# board.net
KiCad netlist of a schematic drawn in EAGLE
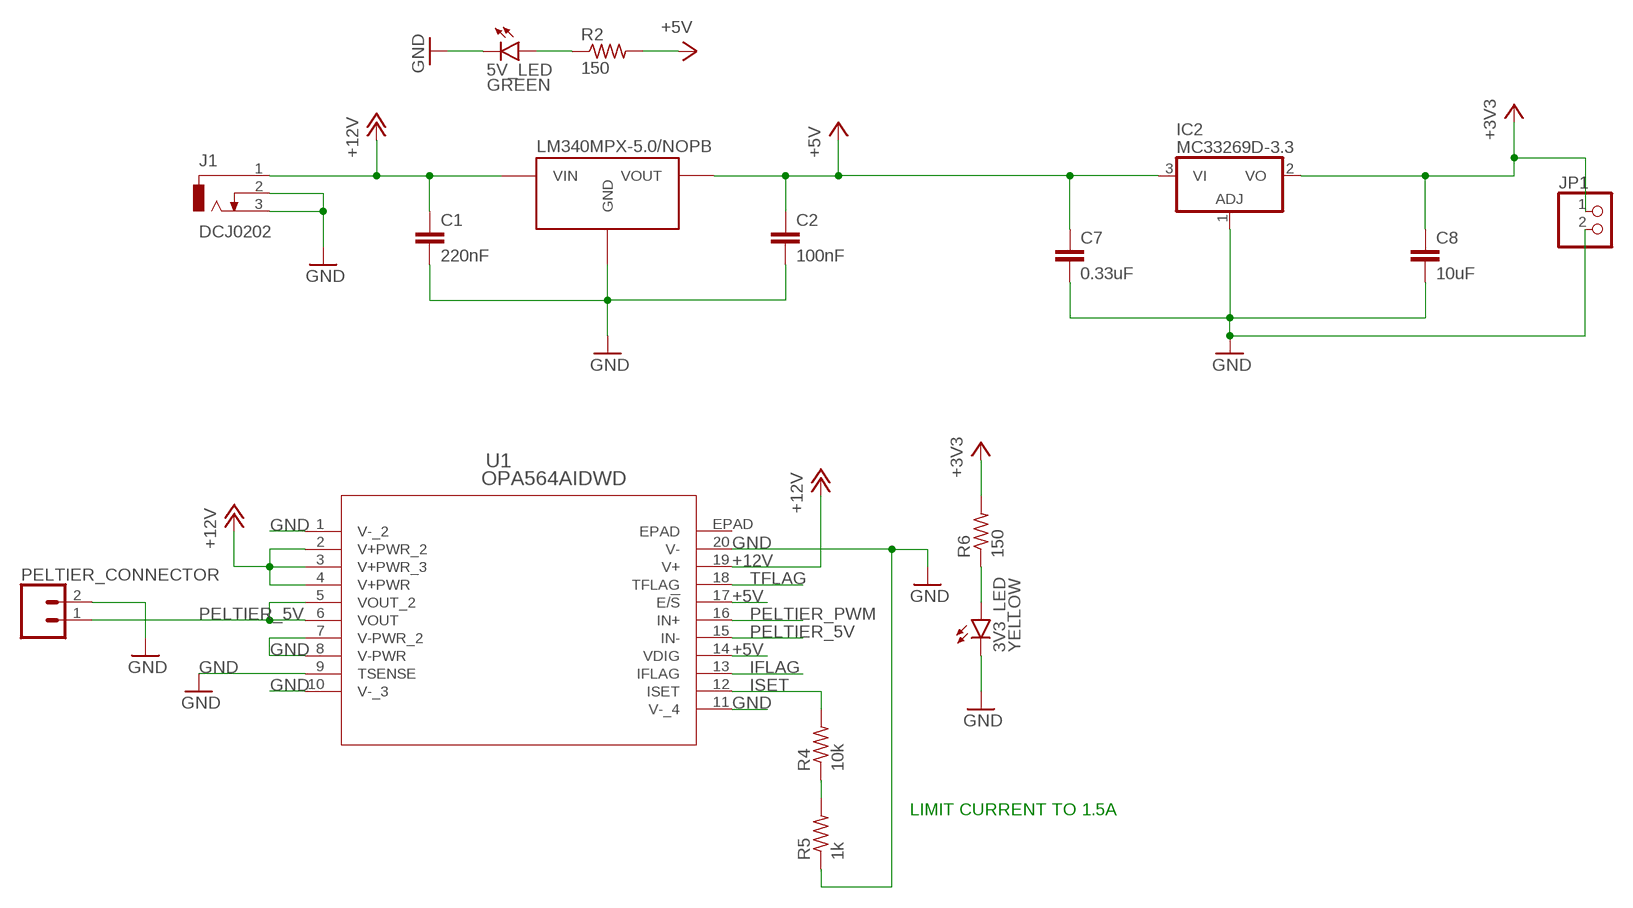
[diagram p0: schematic, sheet 1]
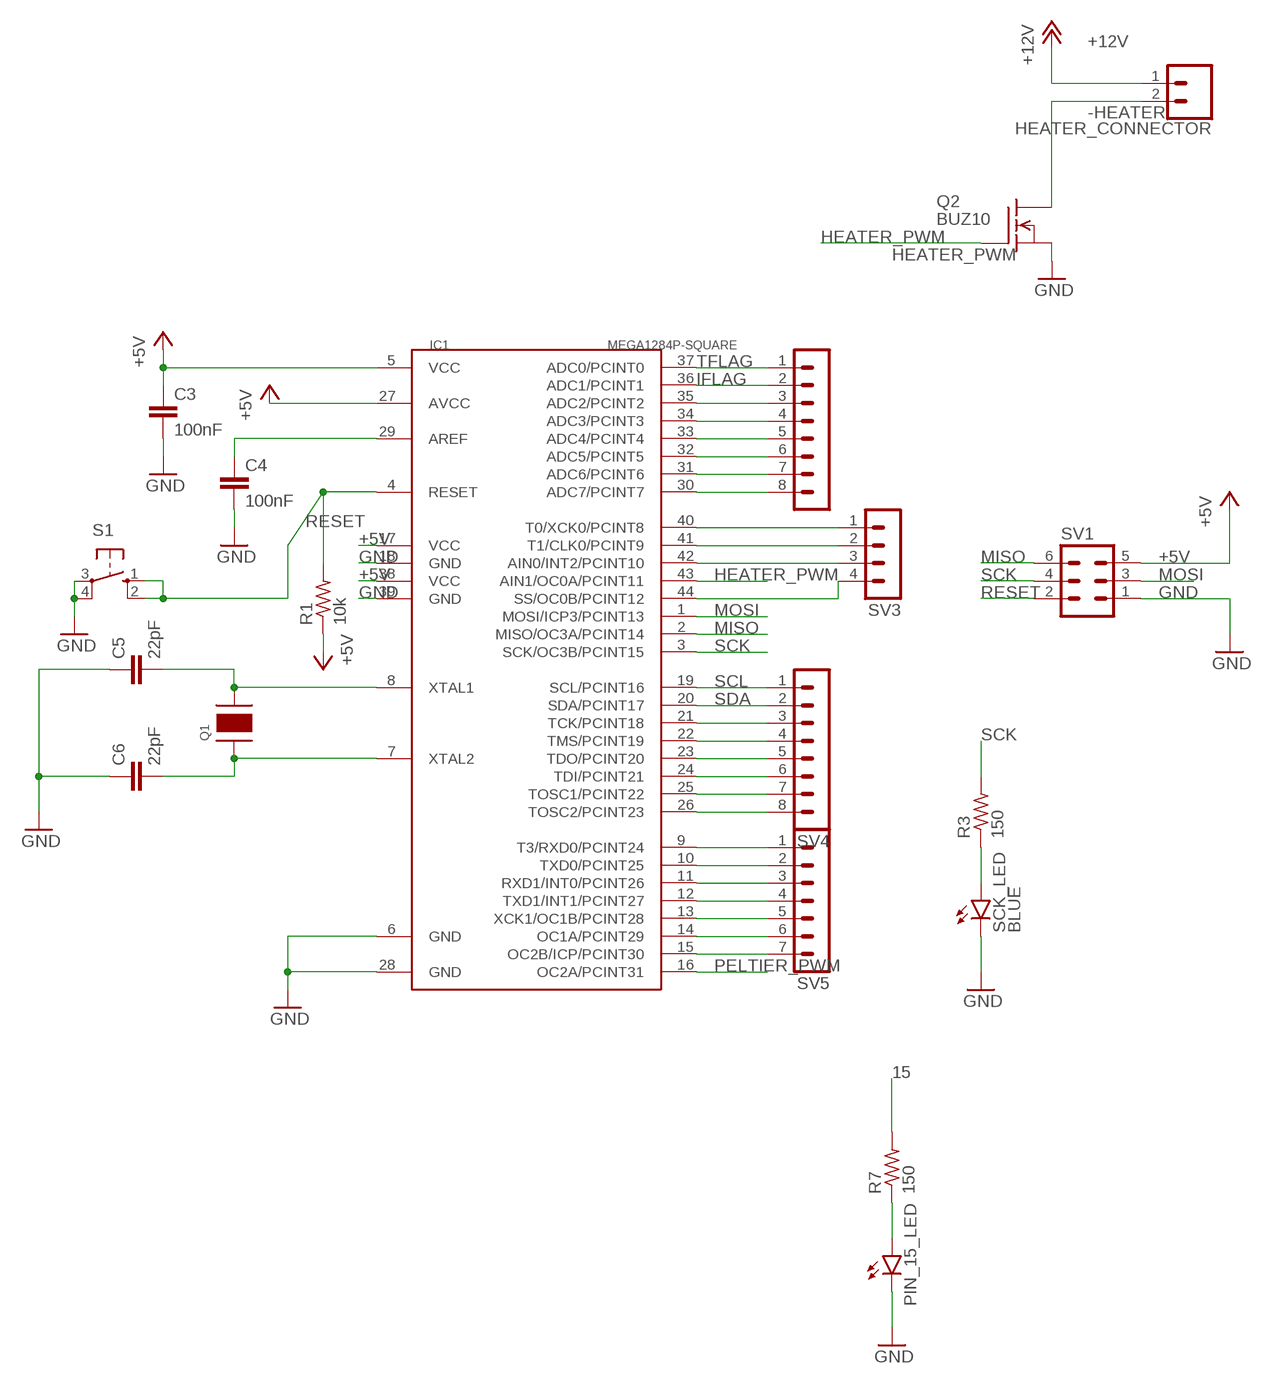
[diagram p1: schematic, sheet 2]

(export (version "E")
  (design (tool "Eeschema 10.0.6"))
  (components
    (comp (ref "3V3_LED")
      (value "YELLOW")
      (footprint "eagle-import:CHIP-LED0603")
      (libsource (lib "eagle-import") (part "LEDCHIP-LED0603"))
    )
    (comp (ref "5V_LED")
      (value "GREEN")
      (footprint "eagle-import:CHIP-LED0603")
      (libsource (lib "eagle-import") (part "LEDCHIP-LED0603"))
    )
    (comp (ref "C1")
      (value "220nF")
      (footprint "eagle-import:C0805")
      (libsource (lib "eagle-import") (part "C-EUC0805"))
    )
    (comp (ref "C2")
      (value "100nF")
      (footprint "eagle-import:C0805")
      (libsource (lib "eagle-import") (part "C-EUC0805"))
    )
    (comp (ref "C7")
      (value "0.33uF")
      (footprint "eagle-import:C0805")
      (libsource (lib "eagle-import") (part "C-EUC0805"))
    )
    (comp (ref "C8")
      (value "10uF")
      (footprint "eagle-import:C0805")
      (libsource (lib "eagle-import") (part "C-EUC0805"))
    )
    (comp (ref "IC2")
      (value "MC33269D-3.3")
      (footprint "eagle-import:DPACK")
      (libsource (lib "eagle-import") (part "MC33269?D-3.3"))
    )
    (comp (ref "J1")
      (value "DCJ0202")
      (footprint "eagle-import:DCJ0202")
      (libsource (lib "eagle-import") (part "DCJ0202"))
    )
    (comp (ref "JP1")
      (value "PINHD-1X2")
      (footprint "eagle-import:1X02")
      (libsource (lib "eagle-import") (part "PINHD-1X2"))
    )
    (comp (ref "LDO1")
      (value "LM340MPX-5.0/NOPB")
      (footprint "eagle-import:SOT-223")
      (libsource (lib "eagle-import") (part "LM340MPX-5.0/NOPB"))
    )
    (comp (ref "PELTIER_CONNECTOR")
      (value "CONN_025MM")
      (footprint "eagle-import:SCREWTERMINAL-5MM-2")
      (libsource (lib "eagle-import") (part "CONN_025MM"))
    )
    (comp (ref "R2")
      (value "150")
      (footprint "eagle-import:R0603")
      (libsource (lib "eagle-import") (part "R-US_R0603"))
    )
    (comp (ref "R4")
      (value "10k")
      (footprint "eagle-import:R0603")
      (libsource (lib "eagle-import") (part "R-US_R0603"))
    )
    (comp (ref "R5")
      (value "1k")
      (footprint "eagle-import:R0603")
      (libsource (lib "eagle-import") (part "R-US_R0603"))
    )
    (comp (ref "R6")
      (value "150")
      (footprint "eagle-import:R0603")
      (libsource (lib "eagle-import") (part "R-US_R0603"))
    )
    (comp (ref "U1")
      (value "OPA564AIDWD")
      (footprint "eagle-import:DWD20_4P62X3P56")
      (libsource (lib "eagle-import") (part "OPA564AIDWD"))
    )
    (comp (ref "C3")
      (value "100nF")
      (footprint "eagle-import:C0603")
      (libsource (lib "eagle-import") (part "C-EUC0603"))
    )
    (comp (ref "C4")
      (value "100nF")
      (footprint "eagle-import:C0603")
      (libsource (lib "eagle-import") (part "C-EUC0603"))
    )
    (comp (ref "C5")
      (value "22pF")
      (footprint "eagle-import:C0603")
      (libsource (lib "eagle-import") (part "C-EUC0603"))
    )
    (comp (ref "C6")
      (value "22pF")
      (footprint "eagle-import:C0603")
      (libsource (lib "eagle-import") (part "C-EUC0603"))
    )
    (comp (ref "HEATER_CONNECTOR")
      (value "CONN_025MM")
      (footprint "eagle-import:SCREWTERMINAL-5MM-2")
      (libsource (lib "eagle-import") (part "CONN_025MM"))
    )
    (comp (ref "IC1")
      (value "MEGA1284P-SQUARE")
      (footprint "eagle-import:TQFP44")
      (libsource (lib "eagle-import") (part "MEGA1284P-SQUARE"))
    )
    (comp (ref "PIN_15_LED")
      (value "BLUE")
      (footprint "eagle-import:CHIP-LED0603")
      (libsource (lib "eagle-import") (part "LEDCHIP-LED0603"))
    )
    (comp (ref "Q1")
      (value "CRYSTAL_16MHZ_SMD")
      (footprint "eagle-import:4-SMD_DFN")
      (libsource (lib "eagle-import") (part "CRYSTAL_16MHZ_SMD"))
    )
    (comp (ref "Q2")
      (value "BUZ10")
      (footprint "eagle-import:TO220")
      (libsource (lib "eagle-import") (part "BUZ10"))
    )
    (comp (ref "R1")
      (value "10k")
      (footprint "eagle-import:R0603")
      (libsource (lib "eagle-import") (part "R-US_R0603"))
    )
    (comp (ref "R3")
      (value "150")
      (footprint "eagle-import:R0603")
      (libsource (lib "eagle-import") (part "R-US_R0603"))
    )
    (comp (ref "R7")
      (value "150")
      (footprint "eagle-import:R0603")
      (libsource (lib "eagle-import") (part "R-US_R0603"))
    )
    (comp (ref "S1")
      (value "10-XX")
      (footprint "eagle-import:B3F-10XX")
      (fields (field (name "MPN") "B3F-1000"))
      (libsource (lib "eagle-import") (part "10-XX"))
    )
    (comp (ref "SCK_LED")
      (value "BLUE")
      (footprint "eagle-import:CHIP-LED0603")
      (libsource (lib "eagle-import") (part "LEDCHIP-LED0603"))
    )
    (comp (ref "SV1")
      (value "MA03-2")
      (footprint "eagle-import:MA03-2")
      (libsource (lib "eagle-import") (part "MA03-2"))
    )
    (comp (ref "SV2")
      (value "MA08-1")
      (footprint "eagle-import:MA08-1")
      (libsource (lib "eagle-import") (part "MA08-1"))
    )
    (comp (ref "SV3")
      (value "MA04-1")
      (footprint "eagle-import:MA04-1")
      (libsource (lib "eagle-import") (part "MA04-1"))
    )
    (comp (ref "SV4")
      (value "MA08-1")
      (footprint "eagle-import:MA08-1")
      (libsource (lib "eagle-import") (part "MA08-1"))
    )
    (comp (ref "SV5")
      (value "MA07-1")
      (footprint "eagle-import:MA07-1")
      (libsource (lib "eagle-import") (part "MA07-1"))
    )
  )
  (nets
    (net (code "1") (name "+3V3") (class "Default")
      (node (ref "C8") (pin "1") (pinfunction "1_1") (pintype "passive"))
      (node (ref "IC2") (pin "2") (pinfunction "VO_2") (pintype "passive"))
      (node (ref "JP1") (pin "1") (pinfunction "1_1") (pintype "passive"))
      (node (ref "R6") (pin "2") (pinfunction "2_2") (pintype "passive"))
    )
    (net (code "2") (name "+5V") (class "Default")
      (node (ref "C2") (pin "1") (pinfunction "1_1") (pintype "passive"))
      (node (ref "C3") (pin "1") (pinfunction "1_1") (pintype "passive"))
      (node (ref "C7") (pin "1") (pinfunction "1_1") (pintype "passive"))
      (node (ref "IC1") (pin "17") (pinfunction "VCC_17") (pintype "bidirectional"))
      (node (ref "IC1") (pin "27") (pinfunction "AVCC_27") (pintype "bidirectional"))
      (node (ref "IC1") (pin "38") (pinfunction "VCC_38") (pintype "bidirectional"))
      (node (ref "IC1") (pin "5") (pinfunction "VCC_5") (pintype "bidirectional"))
      (node (ref "IC2") (pin "3") (pinfunction "VI_3") (pintype "input"))
      (node (ref "LDO1") (pin "P$3") (pinfunction "VOUT_P$3") (pintype "power_in"))
      (node (ref "R1") (pin "1") (pinfunction "1_1") (pintype "passive"))
      (node (ref "R2") (pin "2") (pinfunction "2_2") (pintype "passive"))
      (node (ref "SV1") (pin "5") (pinfunction "5_5") (pintype "passive"))
      (node (ref "U1") (pin "14") (pinfunction "VDIG_14") (pintype "passive"))
      (node (ref "U1") (pin "17") (pinfunction "E/~{S}_17") (pintype "bidirectional"))
    )
    (net (code "3") (name "+12V") (class "Default")
      (node (ref "C1") (pin "1") (pinfunction "1_1") (pintype "passive"))
      (node (ref "HEATER_CONNECTOR") (pin "1") (pinfunction "1_1") (pintype "passive"))
      (node (ref "J1") (pin "1") (pinfunction "1_1") (pintype "passive"))
      (node (ref "LDO1") (pin "P$1") (pinfunction "VIN_P$1") (pintype "input"))
      (node (ref "U1") (pin "19") (pinfunction "V+_19") (pintype "power_in"))
      (node (ref "U1") (pin "2") (pinfunction "V+PWR_2_2") (pintype "power_in"))
      (node (ref "U1") (pin "3") (pinfunction "V+PWR_3_3") (pintype "power_in"))
      (node (ref "U1") (pin "4") (pinfunction "V+PWR_4") (pintype "power_in"))
    )
    (net (code "4") (name "-HEATER") (class "Default")
      (node (ref "HEATER_CONNECTOR") (pin "2") (pinfunction "2_2") (pintype "passive"))
      (node (ref "Q2") (pin "2") (pinfunction "D_2") (pintype "passive"))
    )
    (net (code "5") (name "15") (class "Default")
      (node (ref "IC1") (pin "15") (pinfunction "OC2B/ICP/PCINT30_15") (pintype "bidirectional"))
      (node (ref "R7") (pin "2") (pinfunction "2_2") (pintype "passive"))
      (node (ref "SV5") (pin "7") (pinfunction "7_7") (pintype "passive"))
    )
    (net (code "6") (name "GND") (class "Default")
      (node (ref "3V3_LED") (pin "C") (pinfunction "C_C") (pintype "passive"))
      (node (ref "5V_LED") (pin "C") (pinfunction "C_C") (pintype "passive"))
      (node (ref "C1") (pin "2") (pinfunction "2_2") (pintype "passive"))
      (node (ref "C2") (pin "2") (pinfunction "2_2") (pintype "passive"))
      (node (ref "C3") (pin "2") (pinfunction "2_2") (pintype "passive"))
      (node (ref "C4") (pin "2") (pinfunction "2_2") (pintype "passive"))
      (node (ref "C5") (pin "1") (pinfunction "1_1") (pintype "passive"))
      (node (ref "C6") (pin "1") (pinfunction "1_1") (pintype "passive"))
      (node (ref "C7") (pin "2") (pinfunction "2_2") (pintype "passive"))
      (node (ref "C8") (pin "2") (pinfunction "2_2") (pintype "passive"))
      (node (ref "IC1") (pin "18") (pinfunction "GND_18") (pintype "bidirectional"))
      (node (ref "IC1") (pin "28") (pinfunction "GND_28") (pintype "bidirectional"))
      (node (ref "IC1") (pin "39") (pinfunction "GND_39") (pintype "bidirectional"))
      (node (ref "IC1") (pin "6") (pinfunction "GND_6") (pintype "bidirectional"))
      (node (ref "IC2") (pin "1") (pinfunction "ADJ_1") (pintype "input"))
      (node (ref "J1") (pin "2") (pinfunction "2_2") (pintype "passive"))
      (node (ref "J1") (pin "3") (pinfunction "3_3") (pintype "passive"))
      (node (ref "JP1") (pin "2") (pinfunction "2_2") (pintype "passive"))
      (node (ref "LDO1") (pin "P$2") (pinfunction "GND_P$2") (pintype "input"))
      (node (ref "LDO1") (pin "P$4") (pinfunction "GND_P$4") (pintype "input"))
      (node (ref "PELTIER_CONNECTOR") (pin "2") (pinfunction "2_2") (pintype "passive"))
      (node (ref "PIN_15_LED") (pin "C") (pinfunction "C_C") (pintype "passive"))
      (node (ref "Q2") (pin "3") (pinfunction "S_3") (pintype "passive"))
      (node (ref "R5") (pin "1") (pinfunction "1_1") (pintype "passive"))
      (node (ref "S1") (pin "3") (pinfunction "P_3") (pintype "passive"))
      (node (ref "S1") (pin "4") (pinfunction "P1_4") (pintype "passive"))
      (node (ref "SCK_LED") (pin "C") (pinfunction "C_C") (pintype "passive"))
      (node (ref "SV1") (pin "1") (pinfunction "1_1") (pintype "passive"))
      (node (ref "U1") (pin "1") (pinfunction "V-_2_1") (pintype "power_in"))
      (node (ref "U1") (pin "10") (pinfunction "V-_3_10") (pintype "power_in"))
      (node (ref "U1") (pin "11") (pinfunction "V-_4_11") (pintype "power_in"))
      (node (ref "U1") (pin "20") (pinfunction "V-_20") (pintype "power_in"))
      (node (ref "U1") (pin "7") (pinfunction "V-PWR_2_7") (pintype "power_in"))
      (node (ref "U1") (pin "8") (pinfunction "V-PWR_8") (pintype "power_in"))
      (node (ref "U1") (pin "9") (pinfunction "TSENSE_9") (pintype "passive"))
    )
    (net (code "7") (name "HEATER_PWM") (class "Default")
      (node (ref "IC1") (pin "43") (pinfunction "AIN1/OC0A/PCINT11_43") (pintype "bidirectional"))
      (node (ref "Q2") (pin "1") (pinfunction "G_1") (pintype "passive"))
    )
    (net (code "8") (name "IFLAG") (class "Default")
      (node (ref "IC1") (pin "36") (pinfunction "ADC1/PCINT1_36") (pintype "bidirectional"))
      (node (ref "SV2") (pin "2") (pinfunction "2_2") (pintype "passive"))
      (node (ref "U1") (pin "13") (pinfunction "IFLAG_13") (pintype "passive"))
    )
    (net (code "9") (name "ISET") (class "Default")
      (node (ref "R4") (pin "2") (pinfunction "2_2") (pintype "passive"))
      (node (ref "U1") (pin "12") (pinfunction "ISET_12") (pintype "passive"))
    )
    (net (code "10") (name "MISO") (class "Default")
      (node (ref "IC1") (pin "2") (pinfunction "MISO/OC3A/PCINT14_2") (pintype "bidirectional"))
      (node (ref "SV1") (pin "6") (pinfunction "6_6") (pintype "passive"))
    )
    (net (code "11") (name "MOSI") (class "Default")
      (node (ref "IC1") (pin "1") (pinfunction "MOSI/ICP3/PCINT13_1") (pintype "bidirectional"))
      (node (ref "SV1") (pin "3") (pinfunction "3_3") (pintype "passive"))
    )
    (net (code "12") (name "Net-(3V3_LED-PadA)") (class "Default")
      (node (ref "3V3_LED") (pin "A") (pinfunction "A_A") (pintype "passive"))
      (node (ref "R6") (pin "1") (pinfunction "1_1") (pintype "passive"))
    )
    (net (code "13") (name "Net-(5V_LED-PadA)") (class "Default")
      (node (ref "5V_LED") (pin "A") (pinfunction "A_A") (pintype "passive"))
      (node (ref "R2") (pin "1") (pinfunction "1_1") (pintype "passive"))
    )
    (net (code "14") (name "Net-(IC1-ADC2{slash}PCINT2)") (class "Default")
      (node (ref "IC1") (pin "35") (pinfunction "ADC2/PCINT2_35") (pintype "bidirectional"))
      (node (ref "SV2") (pin "3") (pinfunction "3_3") (pintype "passive"))
    )
    (net (code "15") (name "Net-(IC1-ADC3{slash}PCINT3)") (class "Default")
      (node (ref "IC1") (pin "34") (pinfunction "ADC3/PCINT3_34") (pintype "bidirectional"))
      (node (ref "SV2") (pin "4") (pinfunction "4_4") (pintype "passive"))
    )
    (net (code "16") (name "Net-(IC1-ADC4{slash}PCINT4)") (class "Default")
      (node (ref "IC1") (pin "33") (pinfunction "ADC4/PCINT4_33") (pintype "bidirectional"))
      (node (ref "SV2") (pin "5") (pinfunction "5_5") (pintype "passive"))
    )
    (net (code "17") (name "Net-(IC1-ADC5{slash}PCINT5)") (class "Default")
      (node (ref "IC1") (pin "32") (pinfunction "ADC5/PCINT5_32") (pintype "bidirectional"))
      (node (ref "SV2") (pin "6") (pinfunction "6_6") (pintype "passive"))
    )
    (net (code "18") (name "Net-(IC1-ADC6{slash}PCINT6)") (class "Default")
      (node (ref "IC1") (pin "31") (pinfunction "ADC6/PCINT6_31") (pintype "bidirectional"))
      (node (ref "SV2") (pin "7") (pinfunction "7_7") (pintype "passive"))
    )
    (net (code "19") (name "Net-(IC1-ADC7{slash}PCINT7)") (class "Default")
      (node (ref "IC1") (pin "30") (pinfunction "ADC7/PCINT7_30") (pintype "bidirectional"))
      (node (ref "SV2") (pin "8") (pinfunction "8_8") (pintype "passive"))
    )
    (net (code "20") (name "Net-(IC1-AIN0{slash}INT2{slash}PCINT10)") (class "Default")
      (node (ref "IC1") (pin "42") (pinfunction "AIN0/INT2/PCINT10_42") (pintype "bidirectional"))
      (node (ref "SV3") (pin "3") (pinfunction "3_3") (pintype "passive"))
    )
    (net (code "21") (name "Net-(IC1-AREF)") (class "Default")
      (node (ref "C4") (pin "1") (pinfunction "1_1") (pintype "passive"))
      (node (ref "IC1") (pin "29") (pinfunction "AREF_29") (pintype "bidirectional"))
    )
    (net (code "22") (name "Net-(IC1-OC1A{slash}PCINT29)") (class "Default")
      (node (ref "IC1") (pin "14") (pinfunction "OC1A/PCINT29_14") (pintype "bidirectional"))
      (node (ref "SV5") (pin "6") (pinfunction "6_6") (pintype "passive"))
    )
    (net (code "23") (name "Net-(IC1-RXD1{slash}INT0{slash}PCINT26)") (class "Default")
      (node (ref "IC1") (pin "11") (pinfunction "RXD1/INT0/PCINT26_11") (pintype "bidirectional"))
      (node (ref "SV5") (pin "3") (pinfunction "3_3") (pintype "passive"))
    )
    (net (code "24") (name "Net-(IC1-SS{slash}OC0B{slash}PCINT12)") (class "Default")
      (node (ref "IC1") (pin "44") (pinfunction "SS/OC0B/PCINT12_44") (pintype "bidirectional"))
      (node (ref "SV3") (pin "4") (pinfunction "4_4") (pintype "passive"))
    )
    (net (code "25") (name "Net-(IC1-T0{slash}XCK0{slash}PCINT8)") (class "Default")
      (node (ref "IC1") (pin "40") (pinfunction "T0/XCK0/PCINT8_40") (pintype "bidirectional"))
      (node (ref "SV3") (pin "1") (pinfunction "1_1") (pintype "passive"))
    )
    (net (code "26") (name "Net-(IC1-T1{slash}CLK0{slash}PCINT9)") (class "Default")
      (node (ref "IC1") (pin "41") (pinfunction "T1/CLK0/PCINT9_41") (pintype "bidirectional"))
      (node (ref "SV3") (pin "2") (pinfunction "2_2") (pintype "passive"))
    )
    (net (code "27") (name "Net-(IC1-T3{slash}RXD0{slash}PCINT24)") (class "Default")
      (node (ref "IC1") (pin "9") (pinfunction "T3/RXD0/PCINT24_9") (pintype "bidirectional"))
      (node (ref "SV5") (pin "1") (pinfunction "1_1") (pintype "passive"))
    )
    (net (code "28") (name "Net-(IC1-TCK{slash}PCINT18)") (class "Default")
      (node (ref "IC1") (pin "21") (pinfunction "TCK/PCINT18_21") (pintype "bidirectional"))
      (node (ref "SV4") (pin "3") (pinfunction "3_3") (pintype "passive"))
    )
    (net (code "29") (name "Net-(IC1-TDI{slash}PCINT21)") (class "Default")
      (node (ref "IC1") (pin "24") (pinfunction "TDI/PCINT21_24") (pintype "bidirectional"))
      (node (ref "SV4") (pin "6") (pinfunction "6_6") (pintype "passive"))
    )
    (net (code "30") (name "Net-(IC1-TDO{slash}PCINT20)") (class "Default")
      (node (ref "IC1") (pin "23") (pinfunction "TDO/PCINT20_23") (pintype "bidirectional"))
      (node (ref "SV4") (pin "5") (pinfunction "5_5") (pintype "passive"))
    )
    (net (code "31") (name "Net-(IC1-TMS{slash}PCINT19)") (class "Default")
      (node (ref "IC1") (pin "22") (pinfunction "TMS/PCINT19_22") (pintype "bidirectional"))
      (node (ref "SV4") (pin "4") (pinfunction "4_4") (pintype "passive"))
    )
    (net (code "32") (name "Net-(IC1-TOSC1{slash}PCINT22)") (class "Default")
      (node (ref "IC1") (pin "25") (pinfunction "TOSC1/PCINT22_25") (pintype "bidirectional"))
      (node (ref "SV4") (pin "7") (pinfunction "7_7") (pintype "passive"))
    )
    (net (code "33") (name "Net-(IC1-TOSC2{slash}PCINT23)") (class "Default")
      (node (ref "IC1") (pin "26") (pinfunction "TOSC2/PCINT23_26") (pintype "bidirectional"))
      (node (ref "SV4") (pin "8") (pinfunction "8_8") (pintype "passive"))
    )
    (net (code "34") (name "Net-(IC1-TXD0{slash}PCINT25)") (class "Default")
      (node (ref "IC1") (pin "10") (pinfunction "TXD0/PCINT25_10") (pintype "bidirectional"))
      (node (ref "SV5") (pin "2") (pinfunction "2_2") (pintype "passive"))
    )
    (net (code "35") (name "Net-(IC1-TXD1{slash}INT1{slash}PCINT27)") (class "Default")
      (node (ref "IC1") (pin "12") (pinfunction "TXD1/INT1/PCINT27_12") (pintype "bidirectional"))
      (node (ref "SV5") (pin "4") (pinfunction "4_4") (pintype "passive"))
    )
    (net (code "36") (name "Net-(IC1-XCK1{slash}OC1B{slash}PCINT28)") (class "Default")
      (node (ref "IC1") (pin "13") (pinfunction "XCK1/OC1B/PCINT28_13") (pintype "bidirectional"))
      (node (ref "SV5") (pin "5") (pinfunction "5_5") (pintype "passive"))
    )
    (net (code "37") (name "Net-(IC1-XTAL1)") (class "Default")
      (node (ref "C5") (pin "2") (pinfunction "2_2") (pintype "passive"))
      (node (ref "IC1") (pin "8") (pinfunction "XTAL1_8") (pintype "bidirectional"))
      (node (ref "Q1") (pin "X2") (pinfunction "P$2_X2") (pintype "bidirectional"))
    )
    (net (code "38") (name "Net-(IC1-XTAL2)") (class "Default")
      (node (ref "C6") (pin "2") (pinfunction "2_2") (pintype "passive"))
      (node (ref "IC1") (pin "7") (pinfunction "XTAL2_7") (pintype "bidirectional"))
      (node (ref "Q1") (pin "X1") (pinfunction "P$1_X1") (pintype "bidirectional"))
    )
    (net (code "39") (name "Net-(PIN_15_LED-PadA)") (class "Default")
      (node (ref "PIN_15_LED") (pin "A") (pinfunction "A_A") (pintype "passive"))
      (node (ref "R7") (pin "1") (pinfunction "1_1") (pintype "passive"))
    )
    (net (code "40") (name "Net-(R3-Pad1)") (class "Default")
      (node (ref "R3") (pin "1") (pinfunction "1_1") (pintype "passive"))
      (node (ref "SCK_LED") (pin "A") (pinfunction "A_A") (pintype "passive"))
    )
    (net (code "41") (name "Net-(R4-Pad1)") (class "Default")
      (node (ref "R4") (pin "1") (pinfunction "1_1") (pintype "passive"))
      (node (ref "R5") (pin "2") (pinfunction "2_2") (pintype "passive"))
    )
    (net (code "42") (name "PELTIER_5V") (class "Default")
      (node (ref "PELTIER_CONNECTOR") (pin "1") (pinfunction "1_1") (pintype "passive"))
      (node (ref "U1") (pin "15") (pinfunction "IN-_15") (pintype "input"))
      (node (ref "U1") (pin "5") (pinfunction "VOUT_2_5") (pintype "bidirectional"))
      (node (ref "U1") (pin "6") (pinfunction "VOUT_6") (pintype "bidirectional"))
    )
    (net (code "43") (name "PELTIER_PWM") (class "Default")
      (node (ref "IC1") (pin "16") (pinfunction "OC2A/PCINT31_16") (pintype "bidirectional"))
      (node (ref "U1") (pin "16") (pinfunction "IN+_16") (pintype "input"))
    )
    (net (code "44") (name "RESET") (class "Default")
      (node (ref "IC1") (pin "4") (pinfunction "RESET_4") (pintype "bidirectional"))
      (node (ref "R1") (pin "2") (pinfunction "2_2") (pintype "passive"))
      (node (ref "S1") (pin "1") (pinfunction "S_1") (pintype "passive"))
      (node (ref "S1") (pin "2") (pinfunction "S1_2") (pintype "passive"))
      (node (ref "SV1") (pin "2") (pinfunction "2_2") (pintype "passive"))
    )
    (net (code "45") (name "SCK") (class "Default")
      (node (ref "IC1") (pin "3") (pinfunction "SCK/OC3B/PCINT15_3") (pintype "bidirectional"))
      (node (ref "R3") (pin "2") (pinfunction "2_2") (pintype "passive"))
      (node (ref "SV1") (pin "4") (pinfunction "4_4") (pintype "passive"))
    )
    (net (code "46") (name "SCL") (class "Default")
      (node (ref "IC1") (pin "19") (pinfunction "SCL/PCINT16_19") (pintype "bidirectional"))
      (node (ref "SV4") (pin "1") (pinfunction "1_1") (pintype "passive"))
    )
    (net (code "47") (name "SDA") (class "Default")
      (node (ref "IC1") (pin "20") (pinfunction "SDA/PCINT17_20") (pintype "bidirectional"))
      (node (ref "SV4") (pin "2") (pinfunction "2_2") (pintype "passive"))
    )
    (net (code "48") (name "TFLAG") (class "Default")
      (node (ref "IC1") (pin "37") (pinfunction "ADC0/PCINT0_37") (pintype "bidirectional"))
      (node (ref "SV2") (pin "1") (pinfunction "1_1") (pintype "passive"))
      (node (ref "U1") (pin "18") (pinfunction "TFLAG_18") (pintype "passive"))
    )
    (net (code "49") (name "unconnected-(U1-PadEPAD)") (class "Default")
      (node (ref "U1") (pin "EPAD") (pinfunction "EPAD_EPAD") (pintype "passive"))
    )
  )
)
